# Sheet1.net
KiCad netlist of a schematic drawn in Altium Designer
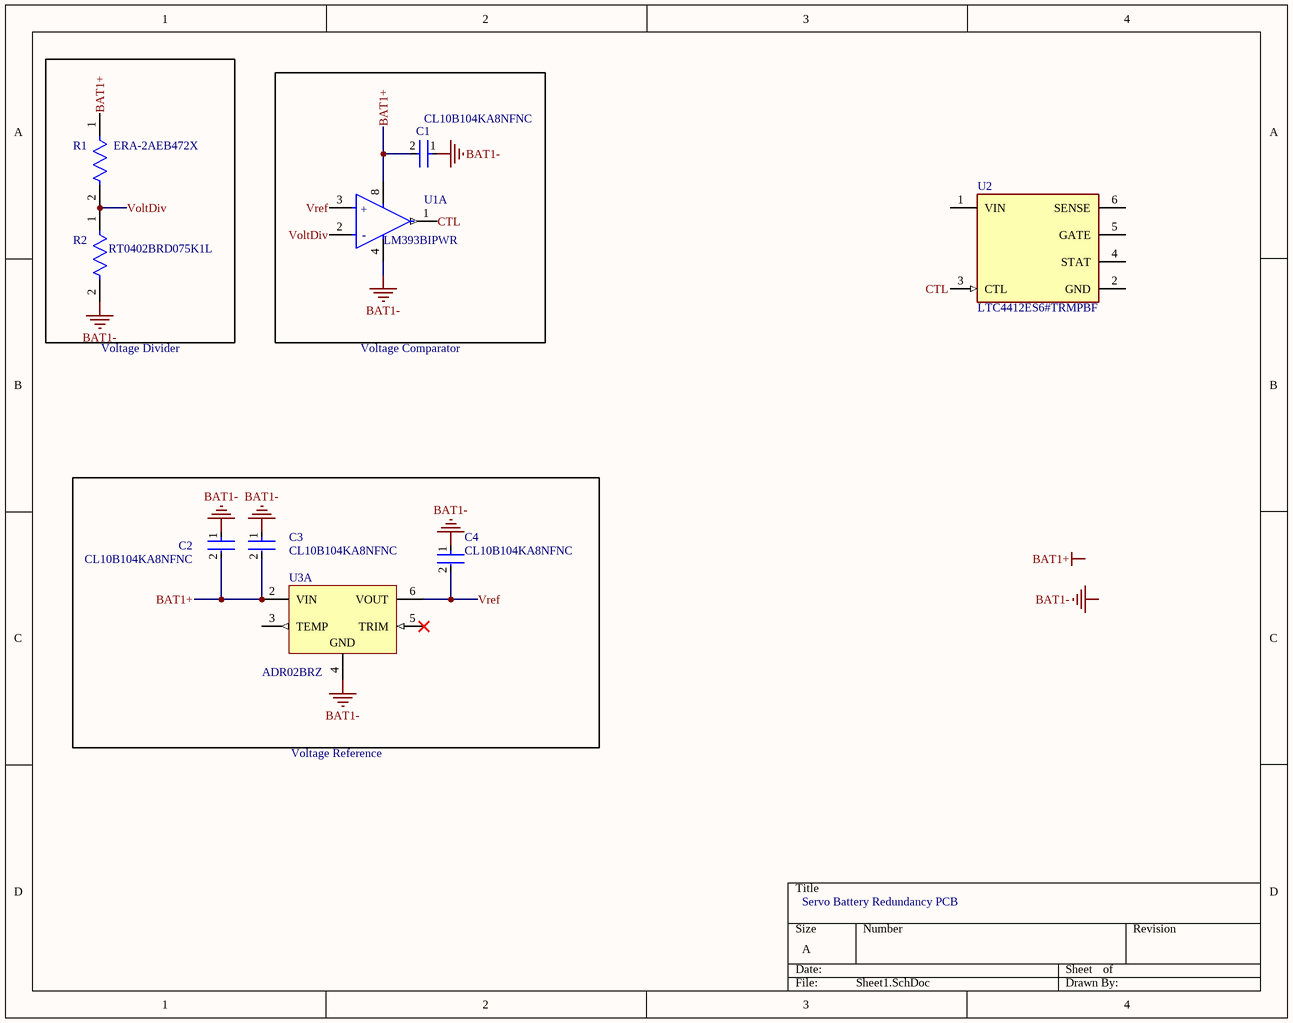
[diagram p0: Sheet1.SchDoc]

(export (version "E")
  (design (tool "Eeschema 10.0.6"))
  (components
    (comp (ref "C1")
      (value "CL10B104KA8NFNC")
      (footprint "FP-CL10-IPC_C")
      (description "Cap Ceramic 100nF 25V X7R ±10% Pad SMD 0603 +125°C T/R")
      (fields (field (name "TOLERANCE") "10%"))
      (libsource (lib "Altium Content Vault") (part "b4654b650e69147ec39a6b967a45e02"))
    )
    (comp (ref "C2")
      (value "CL10B104KA8NFNC")
      (footprint "FP-CL10-IPC_C")
      (description "Cap Ceramic 100nF 25V X7R ±10% Pad SMD 0603 +125°C T/R")
      (fields (field (name "TOLERANCE") "10%"))
      (libsource (lib "Altium Content Vault") (part "b4654b650e69147ec39a6b967a45e02"))
    )
    (comp (ref "C3")
      (value "CL10B104KA8NFNC")
      (footprint "FP-CL10-IPC_C")
      (description "Cap Ceramic 100nF 25V X7R ±10% Pad SMD 0603 +125°C T/R")
      (fields (field (name "TOLERANCE") "10%"))
      (libsource (lib "Altium Content Vault") (part "b4654b650e69147ec39a6b967a45e02"))
    )
    (comp (ref "C4")
      (value "CL10B104KA8NFNC")
      (footprint "FP-CL10-IPC_C")
      (description "Cap Ceramic 100nF 25V X7R ±10% Pad SMD 0603 +125°C T/R")
      (fields (field (name "TOLERANCE") "10%"))
      (libsource (lib "Altium Content Vault") (part "b4654b650e69147ec39a6b967a45e02"))
    )
    (comp (ref "R1")
      (value "ERA-2AEB472X")
      (footprint "FP-ERA2A-IPC_A")
      (description "RES SMD 4.7K OHM 0.1% 1/16W 0402")
      (fields (field (name "TOLERANCE") "0.1%"))
      (libsource (lib "Altium Content Vault") (part "1029c3af85768c4190bb7ad29bc67b5"))
    )
    (comp (ref "R2")
      (value "RT0402BRD075K1L")
      (footprint "FP-RT0402-MFG")
      (description "RES SMD 5.1K OHM 0.1% 1/16W 0402")
      (fields
        (field (name "OCTOPART") "https://octopart.com/rt0402brd075k1l-yageo-1430932")
        (field (name "MANUFACTURER") "Yageo")
      )
      (libsource (lib "Altium Content Vault") (part "1029c3af85768c4190bb7ad29bc67b5"))
    )
    (comp (ref "U1")
      (value "LM393BIPWR")
      (footprint "FP-PW0008A-MFG")
      (description "Dual Comparators")
      (fields
        (field (name "MANUFACTURER") "Texas Instruments")
        (field (name "OCTOPART") "https://octopart.com/lm393bipwr-texas+instruments-107383910")
      )
      (libsource (lib "Altium Content Vault") (part "d0dfe35d032f86ae96c0c3919f86c94"))
    )
    (comp (ref "U2")
      (value "LTC4412ES6#TRMPBF")
      (footprint "FP-S6-6-05-08-1636-IPC_C")
      (description "IC OR CTRLR SRC SELECT TSOT23-6")
      (libsource (lib "Altium Content Vault") (part "07cb0f4431a3a7488227ca1baae77bb"))
    )
    (comp (ref "U3")
      (value "ADR02BRZ")
      (footprint "ADI-R-8_L")
      (fields (field (name "MANUFACTURER") "Analog Devices"))
      (libsource (lib "Altium Content Vault") (part "ADI-REF0x_ADR0x-X-8"))
    )
  )
  (nets
    (net (code "1") (name "/CTL") (class "Default")
      (node (ref "U1") (pin "1") (pinfunction "1OUT_1") (pintype "output"))
      (node (ref "U2") (pin "3") (pinfunction "CTL_3") (pintype "input"))
    )
    (net (code "2") (name "/VoltDiv") (class "Default")
      (node (ref "R1") (pin "2") (pinfunction "2_2") (pintype "passive"))
      (node (ref "R2") (pin "1") (pinfunction "1_1") (pintype "passive"))
      (node (ref "U1") (pin "2") (pinfunction "1IN-_2") (pintype "tri_state"))
    )
    (net (code "3") (name "/Vref") (class "Default")
      (node (ref "C4") (pin "2") (pinfunction "2_2") (pintype "passive"))
      (node (ref "U1") (pin "3") (pinfunction "1IN+_3") (pintype "tri_state"))
      (node (ref "U3") (pin "6") (pinfunction "VOUT_6") (pintype "power_in"))
    )
    (net (code "4") (name "BAT1+") (class "Default")
      (node (ref "C1") (pin "2") (pinfunction "2_2") (pintype "passive"))
      (node (ref "C2") (pin "2") (pinfunction "2_2") (pintype "passive"))
      (node (ref "C3") (pin "2") (pinfunction "2_2") (pintype "passive"))
      (node (ref "R1") (pin "1") (pinfunction "1_1") (pintype "passive"))
      (node (ref "U1") (pin "8") (pinfunction "VCC_8") (pintype "power_in"))
      (node (ref "U3") (pin "2") (pinfunction "VIN_2") (pintype "power_in"))
    )
    (net (code "5") (name "BAT1-") (class "Default")
      (node (ref "C1") (pin "1") (pinfunction "1_1") (pintype "passive"))
      (node (ref "C2") (pin "1") (pinfunction "1_1") (pintype "passive"))
      (node (ref "C3") (pin "1") (pinfunction "1_1") (pintype "passive"))
      (node (ref "C4") (pin "1") (pinfunction "1_1") (pintype "passive"))
      (node (ref "R2") (pin "2") (pinfunction "2_2") (pintype "passive"))
      (node (ref "U1") (pin "4") (pinfunction "GND_4") (pintype "power_in"))
      (node (ref "U3") (pin "4") (pinfunction "GND_4") (pintype "power_in"))
    )
    (net (code "6") (name "unconnected-(U2-GATE-Pad5)") (class "Default")
      (node (ref "U2") (pin "5") (pinfunction "GATE_5") (pintype "passive"))
    )
    (net (code "7") (name "unconnected-(U2-GND-Pad2)") (class "Default")
      (node (ref "U2") (pin "2") (pinfunction "GND_2") (pintype "power_in"))
    )
    (net (code "8") (name "unconnected-(U2-SENSE-Pad6)") (class "Default")
      (node (ref "U2") (pin "6") (pinfunction "SENSE_6") (pintype "passive"))
    )
    (net (code "9") (name "unconnected-(U2-STAT-Pad4)") (class "Default")
      (node (ref "U2") (pin "4") (pinfunction "STAT_4") (pintype "open_collector"))
    )
    (net (code "10") (name "unconnected-(U2-VIN-Pad1)") (class "Default")
      (node (ref "U2") (pin "1") (pinfunction "VIN_1") (pintype "power_in"))
    )
    (net (code "11") (name "unconnected-(U3A-TEMP-Pad3)") (class "Default")
      (node (ref "U3") (pin "3") (pinfunction "TEMP_3") (pintype "output"))
    )
    (net (code "12") (name "unconnected-(U3A-TRIM-Pad5)") (class "Default")
      (node (ref "U3") (pin "5") (pinfunction "TRIM_5") (pintype "input+no_connect"))
    )
  )
)
